# Gatetreiber.net
KiCad netlist of a schematic drawn in Altium Designer
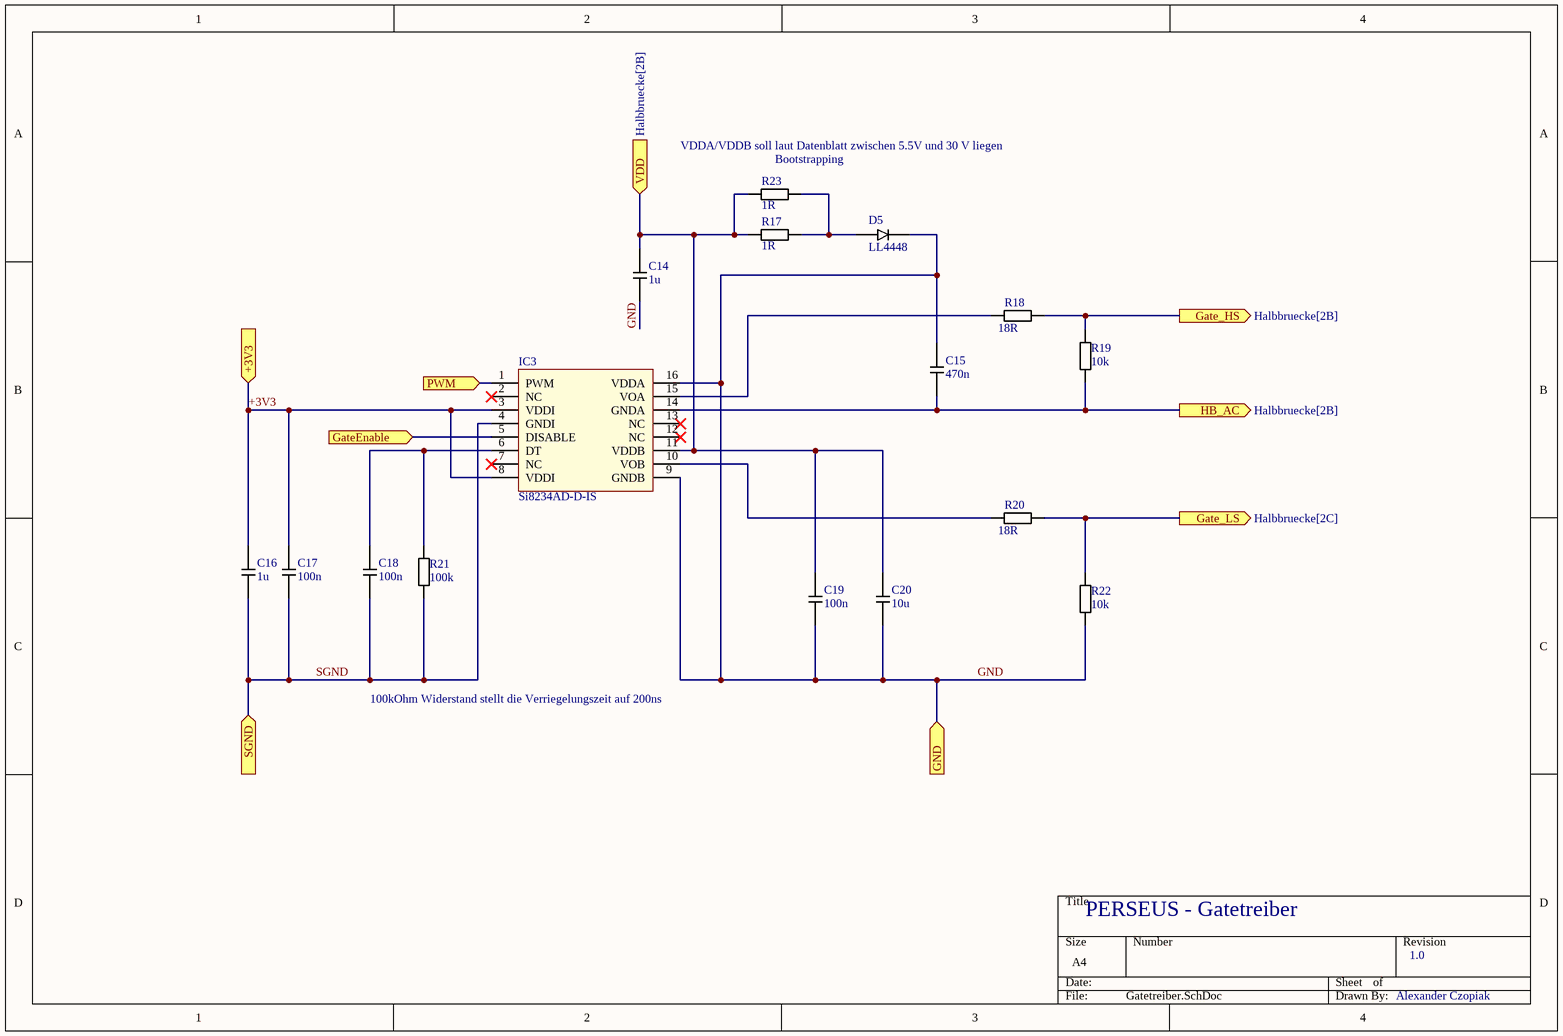
[diagram p0: Gatetreiber.SchDoc]

(export (version "E")
  (design (tool "Eeschema 10.0.6"))
  (components
    (comp (ref "C14")
      (value "1u")
      (footprint "1206_C")
      (description "Kondensator (ohne Polarität)")
      (libsource (lib "HSLS_Parts") (part "CAP"))
    )
    (comp (ref "C15")
      (value "470n")
      (footprint "1206_C")
      (description "Kondensator (ohne Polarität)")
      (libsource (lib "HSLS_Parts") (part "CAP"))
    )
    (comp (ref "C16")
      (value "1u")
      (footprint "1206_C")
      (description "Kondensator (ohne Polarität)")
      (libsource (lib "HSLS_Parts") (part "CAP"))
    )
    (comp (ref "C17")
      (value "100n")
      (footprint "1206_C")
      (description "Kondensator (ohne Polarität)")
      (libsource (lib "HSLS_Parts") (part "CAP"))
    )
    (comp (ref "C18")
      (value "100n")
      (footprint "1206_C")
      (description "Kondensator (ohne Polarität)")
      (libsource (lib "HSLS_Parts") (part "CAP"))
    )
    (comp (ref "C19")
      (value "100n")
      (footprint "1206_C")
      (description "Kondensator (ohne Polarität)")
      (libsource (lib "HSLS_Parts") (part "CAP"))
    )
    (comp (ref "C20")
      (value "10u")
      (footprint "1206_C")
      (description "Kondensator (ohne Polarität)")
      (libsource (lib "HSLS_Parts") (part "CAP"))
    )
    (comp (ref "D5")
      (value "LL4448")
      (footprint "MINIMELF-SOD80")
      (description "Diode (z.B. 1N4448)")
      (libsource (lib "HSLS_Parts") (part "DIODE"))
    )
    (comp (ref "IC3")
      (value "Si8234AD-D-IS")
      (footprint "SO16_W")
      (libsource (lib "HSLS_Parts") (part "Si8234AD-D-IS"))
    )
    (comp (ref "R17")
      (value "1R")
      (footprint "1206_R")
      (description "Widerstand")
      (libsource (lib "") (part "WIDERSTAND_1"))
    )
    (comp (ref "R18")
      (value "18R")
      (footprint "1206_R")
      (description "Widerstand")
      (libsource (lib "") (part "WIDERSTAND_1"))
    )
    (comp (ref "R19")
      (value "10k")
      (footprint "1206_R")
      (description "Widerstand")
      (libsource (lib "HSLS_Parts") (part "WIDERSTAND"))
    )
    (comp (ref "R20")
      (value "18R")
      (footprint "1206_R")
      (description "Widerstand")
      (libsource (lib "") (part "WIDERSTAND_1"))
    )
    (comp (ref "R21")
      (value "100k")
      (footprint "1206_R")
      (description "Widerstand")
      (libsource (lib "") (part "WIDERSTAND_2"))
    )
    (comp (ref "R22")
      (value "10k")
      (footprint "1206_R")
      (description "Widerstand")
      (libsource (lib "") (part "WIDERSTAND_2"))
    )
    (comp (ref "R23")
      (value "1R")
      (footprint "1206_R")
      (description "Widerstand")
      (libsource (lib "") (part "WIDERSTAND_1"))
    )
  )
  (nets
    (net (code "1") (name "/+3V3") (class "Default")
      (node (ref "C16") (pin "2") (pinfunction "2_2") (pintype "passive"))
      (node (ref "C17") (pin "2") (pinfunction "2_2") (pintype "passive"))
      (node (ref "IC3") (pin "3") (pinfunction "VDDI_3") (pintype "passive"))
      (node (ref "IC3") (pin "8") (pinfunction "VDDI_8") (pintype "passive"))
    )
    (net (code "2") (name "/GND") (class "Default")
      (node (ref "C14") (pin "1") (pinfunction "1_1") (pintype "passive"))
      (node (ref "C15") (pin "2") (pinfunction "2_2") (pintype "passive"))
      (node (ref "C19") (pin "1") (pinfunction "1_1") (pintype "passive"))
      (node (ref "C20") (pin "1") (pinfunction "1_1") (pintype "passive"))
      (node (ref "D5") (pin "2") (pinfunction "K_2") (pintype "passive"))
      (node (ref "IC3") (pin "16") (pinfunction "VDDA_16") (pintype "passive"))
      (node (ref "IC3") (pin "9") (pinfunction "GNDB_9") (pintype "passive"))
      (node (ref "R22") (pin "1") (pinfunction "1_1") (pintype "passive"))
    )
    (net (code "3") (name "/GateEnable") (class "Default")
      (node (ref "IC3") (pin "5") (pinfunction "DISABLE_5") (pintype "passive"))
    )
    (net (code "4") (name "/Gate_HS") (class "Default")
      (node (ref "R18") (pin "2") (pinfunction "2_2") (pintype "passive"))
      (node (ref "R19") (pin "1") (pinfunction "1_1") (pintype "passive"))
    )
    (net (code "5") (name "/Gate_LS") (class "Default")
      (node (ref "R20") (pin "2") (pinfunction "2_2") (pintype "passive"))
      (node (ref "R22") (pin "2") (pinfunction "2_2") (pintype "passive"))
    )
    (net (code "6") (name "/HB_AC") (class "Default")
      (node (ref "C15") (pin "1") (pinfunction "1_1") (pintype "passive"))
      (node (ref "IC3") (pin "14") (pinfunction "GNDA_14") (pintype "passive"))
      (node (ref "R19") (pin "2") (pinfunction "2_2") (pintype "passive"))
    )
    (net (code "7") (name "/PWM") (class "Default")
      (node (ref "IC3") (pin "1") (pinfunction "PWM_1") (pintype "passive"))
    )
    (net (code "8") (name "/SGND") (class "Default")
      (node (ref "C16") (pin "1") (pinfunction "1_1") (pintype "passive"))
      (node (ref "C17") (pin "1") (pinfunction "1_1") (pintype "passive"))
      (node (ref "C18") (pin "1") (pinfunction "1_1") (pintype "passive"))
      (node (ref "IC3") (pin "4") (pinfunction "GNDI_4") (pintype "passive"))
      (node (ref "R21") (pin "1") (pinfunction "1_1") (pintype "passive"))
    )
    (net (code "9") (name "/VDD") (class "Default")
      (node (ref "C14") (pin "2") (pinfunction "2_2") (pintype "passive"))
      (node (ref "C19") (pin "2") (pinfunction "2_2") (pintype "passive"))
      (node (ref "C20") (pin "2") (pinfunction "2_2") (pintype "passive"))
      (node (ref "IC3") (pin "11") (pinfunction "VDDB_11") (pintype "passive"))
      (node (ref "R17") (pin "1") (pinfunction "1_1") (pintype "passive"))
      (node (ref "R23") (pin "1") (pinfunction "1_1") (pintype "passive"))
    )
    (net (code "10") (name "Net-(D5-A)") (class "Default")
      (node (ref "D5") (pin "1") (pinfunction "A_1") (pintype "passive"))
      (node (ref "R17") (pin "2") (pinfunction "2_2") (pintype "passive"))
      (node (ref "R23") (pin "2") (pinfunction "2_2") (pintype "passive"))
    )
    (net (code "11") (name "Net-(IC3-DT)") (class "Default")
      (node (ref "C18") (pin "2") (pinfunction "2_2") (pintype "passive"))
      (node (ref "IC3") (pin "6") (pinfunction "DT_6") (pintype "passive"))
      (node (ref "R21") (pin "2") (pinfunction "2_2") (pintype "passive"))
    )
    (net (code "12") (name "Net-(IC3-VOA)") (class "Default")
      (node (ref "IC3") (pin "15") (pinfunction "VOA_15") (pintype "passive"))
      (node (ref "R18") (pin "1") (pinfunction "1_1") (pintype "passive"))
    )
    (net (code "13") (name "Net-(IC3-VOB)") (class "Default")
      (node (ref "IC3") (pin "10") (pinfunction "VOB_10") (pintype "passive"))
      (node (ref "R20") (pin "1") (pinfunction "1_1") (pintype "passive"))
    )
    (net (code "14") (name "unconnected-(IC3-NC-Pad2)") (class "Default")
      (node (ref "IC3") (pin "2") (pinfunction "NC_2") (pintype "passive+no_connect"))
    )
    (net (code "15") (name "unconnected-(IC3-NC-Pad7)") (class "Default")
      (node (ref "IC3") (pin "7") (pinfunction "NC_7") (pintype "passive+no_connect"))
    )
    (net (code "16") (name "unconnected-(IC3-NC-Pad12)") (class "Default")
      (node (ref "IC3") (pin "12") (pinfunction "NC_12") (pintype "passive+no_connect"))
    )
    (net (code "17") (name "unconnected-(IC3-NC-Pad13)") (class "Default")
      (node (ref "IC3") (pin "13") (pinfunction "NC_13") (pintype "passive+no_connect"))
    )
  )
)
